# 1-Schematic_EMWAVER_DIY_V2.net
KiCad netlist of a schematic drawn in EasyEDA
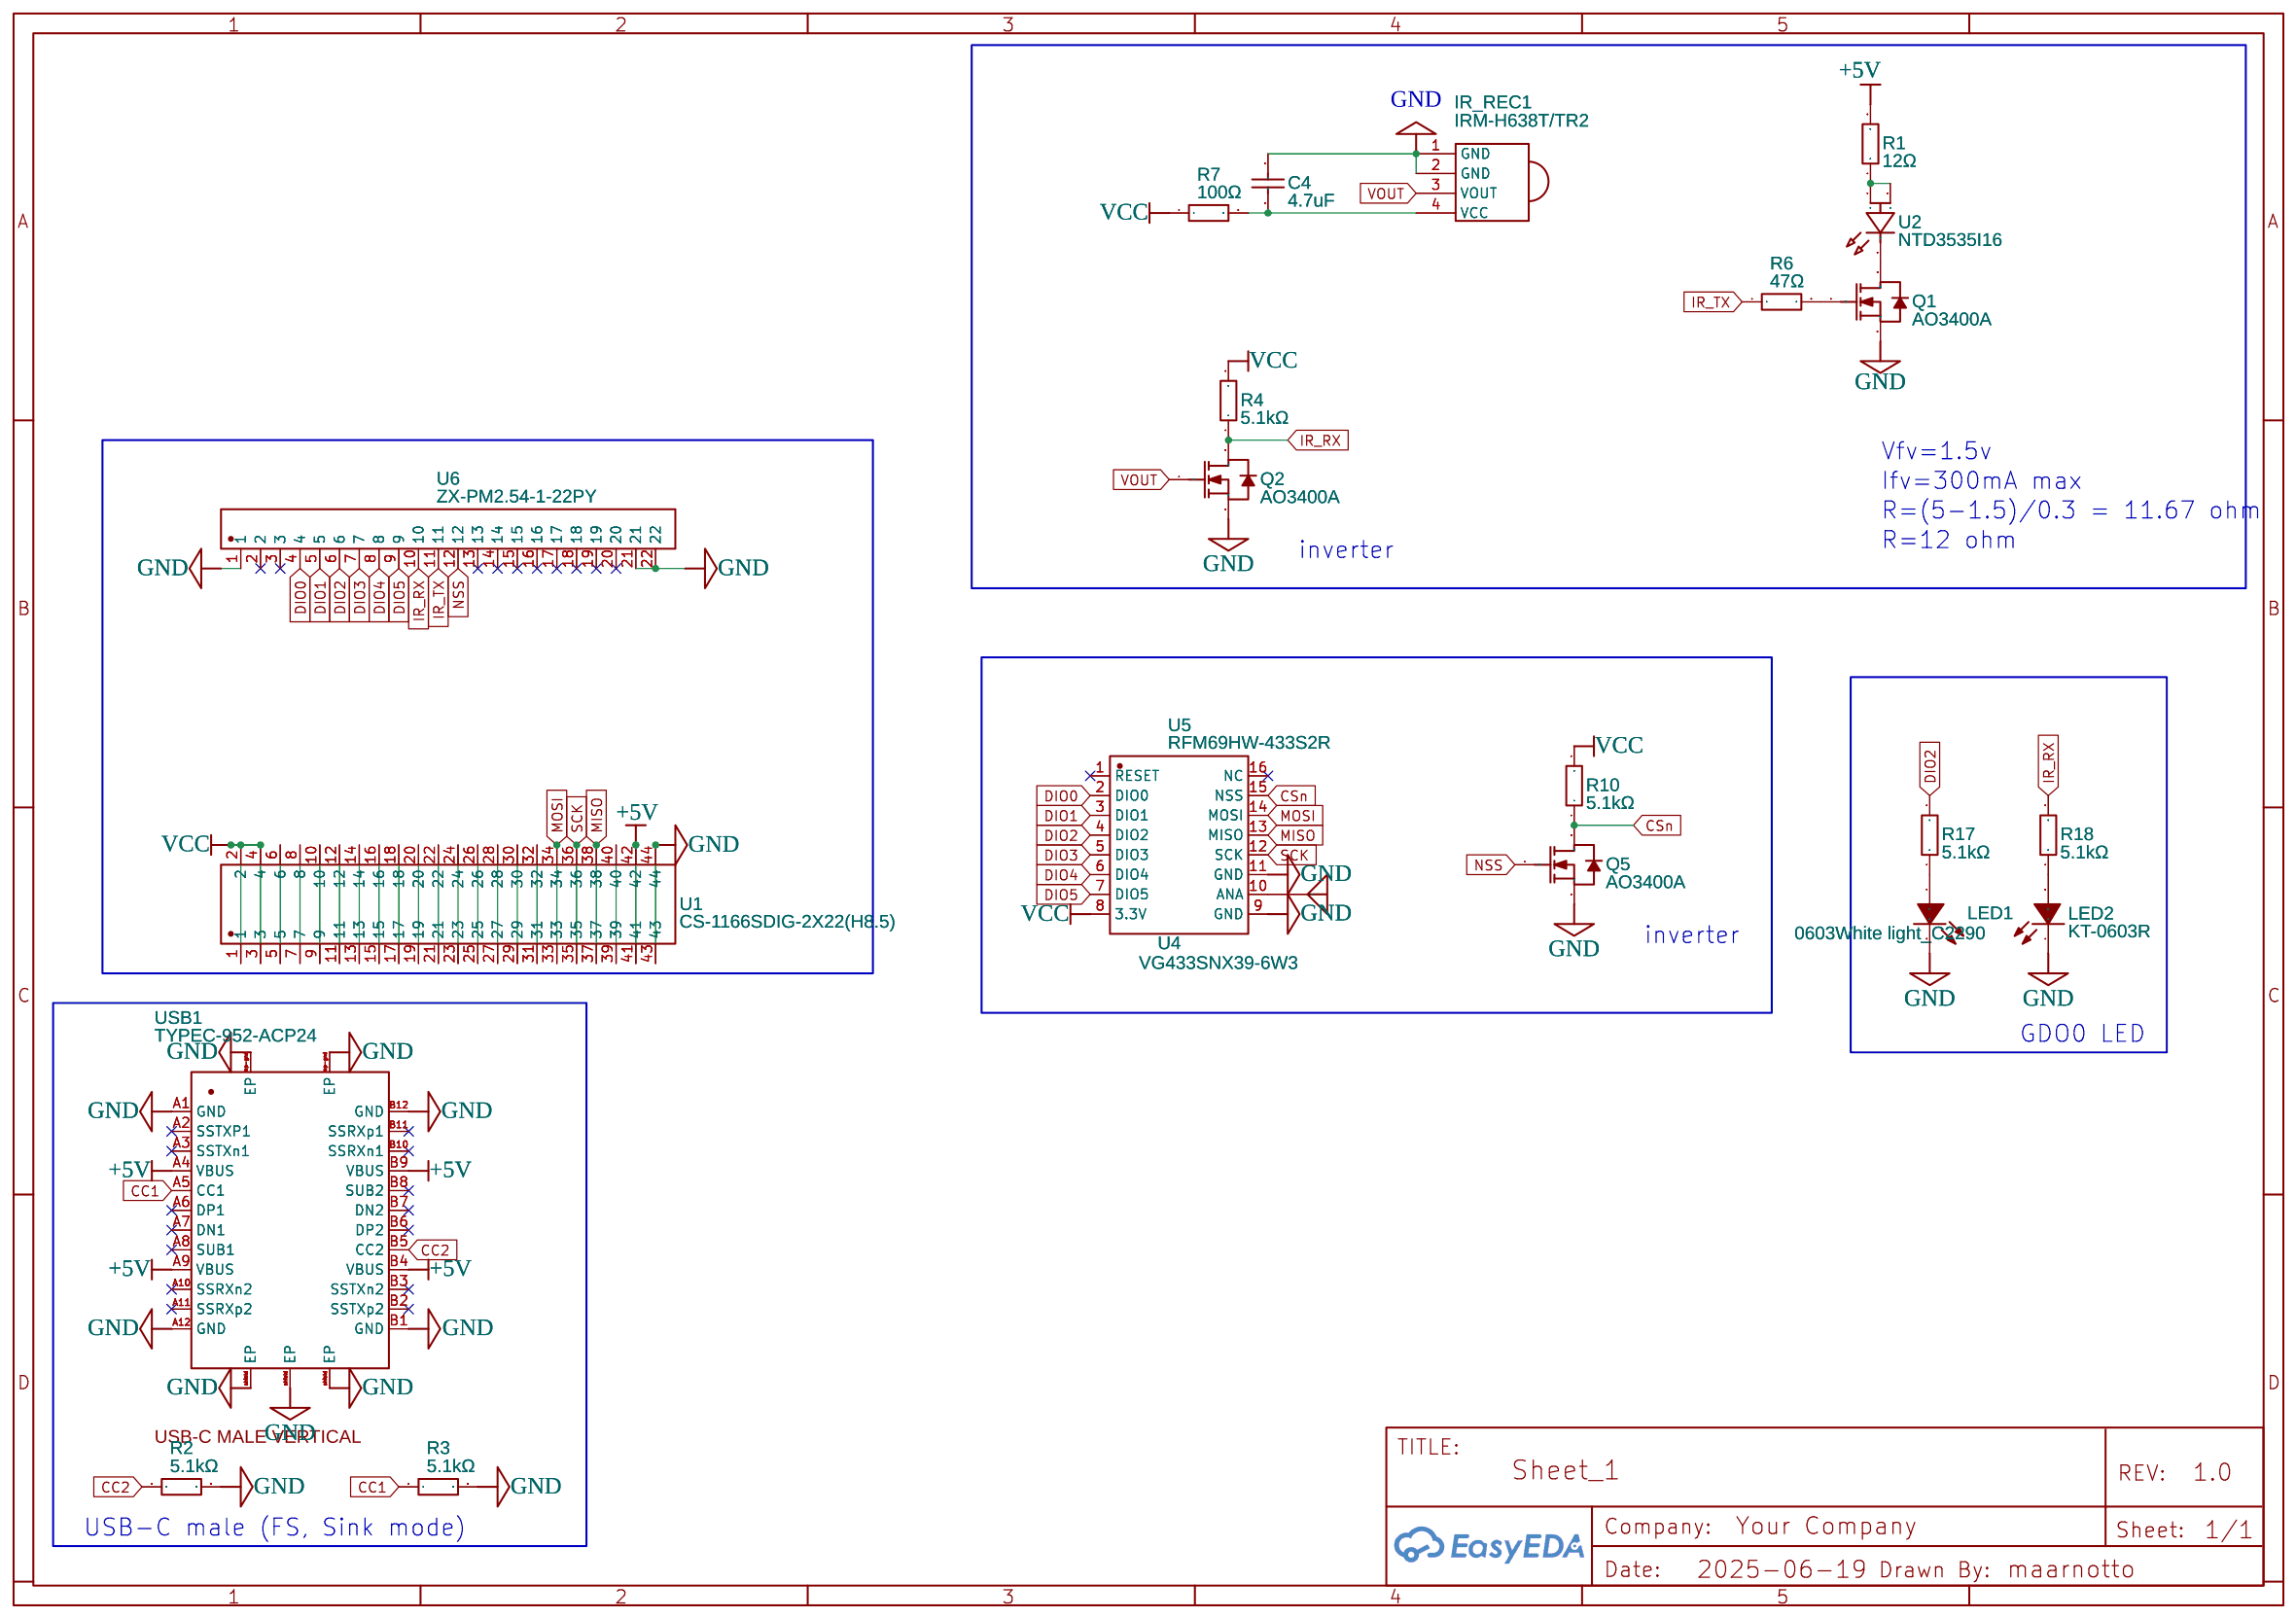
[diagram p0: schematic sheet]

(export (version "E")
  (design (tool "Eeschema 10.0.6"))
  (components
    (comp (ref "C4")
      (value "4.7uF")
      (fields
        (field (name "Manufacturer Part") "CL10A475KO8NNNC")
        (field (name "Manufacturer") "SAMSUNG(三星)")
      )
      (libsource (lib "") (part "CL10A475KO8NNNC"))
    )
    (comp (ref "IR_REC1")
      (value "IRM-H638T/TR2")
      (fields (field (name "Manufacturer") "EVERLIGHT(亿光)"))
      (libsource (lib "") (part "IRM-H638T/TR2"))
    )
    (comp (ref "LED1")
      (value "0603White light_C2290")
      (fields (field (name "Manufacturer Part") "KT-0603W") (field (name "Manufacturer") "KENTO"))
      (libsource (lib "") (part "0603White light_C2290"))
    )
    (comp (ref "LED2")
      (value "KT-0603R")
      (fields (field (name "Manufacturer") "KENTO"))
      (libsource (lib "") (part "KT-0603R"))
    )
    (comp (ref "Q1")
      (value "AO3400A")
      (fields (field (name "Manufacturer") "AOS"))
      (libsource (lib "") (part "AO3400A"))
    )
    (comp (ref "Q2")
      (value "AO3400A")
      (fields (field (name "Manufacturer") "AOS"))
      (libsource (lib "") (part "AO3400A"))
    )
    (comp (ref "Q5")
      (value "AO3400A")
      (fields (field (name "Manufacturer") "AOS"))
      (libsource (lib "") (part "AO3400A"))
    )
    (comp (ref "R1")
      (value "12Ω")
      (fields
        (field (name "Manufacturer Part") "25121WJ0120T4E")
        (field (name "Manufacturer") "UNI-ROYAL(厚声)")
      )
      (libsource (lib "") (part "25121WJ0120T4E"))
    )
    (comp (ref "R2")
      (value "5.1kΩ")
      (fields
        (field (name "Manufacturer Part") "0603WAF5101T5E")
        (field (name "Manufacturer") "UNI-ROYAL(厚声)")
      )
      (libsource (lib "") (part "0603WAF5101T5E_1"))
    )
    (comp (ref "R3")
      (value "5.1kΩ")
      (fields
        (field (name "Manufacturer Part") "0603WAF5101T5E")
        (field (name "Manufacturer") "UNI-ROYAL(厚声)")
      )
      (libsource (lib "") (part "0603WAF5101T5E_1"))
    )
    (comp (ref "R4")
      (value "5.1kΩ")
      (fields
        (field (name "Manufacturer Part") "0603WAF5101T5E")
        (field (name "Manufacturer") "UNI-ROYAL(厚声)")
      )
      (libsource (lib "") (part "0603WAF5101T5E"))
    )
    (comp (ref "R6")
      (value "47Ω")
      (fields
        (field (name "Manufacturer Part") "0805W8F470JT5E")
        (field (name "Manufacturer") "UNI-ROYAL(厚声)")
      )
      (libsource (lib "") (part "0805W8F470JT5E"))
    )
    (comp (ref "R7")
      (value "100Ω")
      (fields
        (field (name "Manufacturer Part") "0805W8F1000T5E")
        (field (name "Manufacturer") "UNI-ROYAL(厚声)")
      )
      (libsource (lib "") (part "0805W8F1000T5E"))
    )
    (comp (ref "R10")
      (value "5.1kΩ")
      (fields
        (field (name "Manufacturer Part") "0603WAF5101T5E")
        (field (name "Manufacturer") "UNI-ROYAL(厚声)")
      )
      (libsource (lib "") (part "0603WAF5101T5E"))
    )
    (comp (ref "R17")
      (value "5.1kΩ")
      (fields
        (field (name "Manufacturer Part") "0603WAF5101T5E")
        (field (name "Manufacturer") "UNI-ROYAL(厚声)")
      )
      (libsource (lib "") (part "0603WAF5101T5E"))
    )
    (comp (ref "R18")
      (value "5.1kΩ")
      (fields
        (field (name "Manufacturer Part") "0603WAF5101T5E")
        (field (name "Manufacturer") "UNI-ROYAL(厚声)")
      )
      (libsource (lib "") (part "0603WAF5101T5E"))
    )
    (comp (ref "U1")
      (value "CS-1166SDIG-2X22(H8.5)")
      (fields (field (name "Manufacturer") "CST(永丰盈)"))
      (libsource (lib "") (part "CS-1166SDIG-2X22(H8.5)"))
    )
    (comp (ref "U2")
      (value "NTD3535I16")
      (fields (field (name "Manufacturer") "国星光电"))
      (libsource (lib "") (part "NTD3535I16"))
    )
    (comp (ref "U4")
      (value "VG433SNX39-6W3")
      (fields (field (name "Manufacturer") "Vollgo(沃进)"))
      (libsource (lib "") (part "VG433SNX39-6W3"))
    )
    (comp (ref "U5") (value "RFM69HW-433S2R") (libsource (lib "") (part "RFM69HW-433S2R")))
    (comp (ref "U6")
      (value "ZX-PM2.54-1-22PY")
      (fields (field (name "Manufacturer") "Megastar(兆星)"))
      (libsource (lib "") (part "ZX-PM2.54-1-22PY"))
    )
    (comp (ref "USB1")
      (value "TYPEC-952-ACP24")
      (fields (field (name "Manufacturer") "XUNPU(讯普)"))
      (libsource (lib "") (part "TYPEC-952-ACP24"))
    )
  )
  (nets
    (net (code "1") (name "+5V") (class "Default")
      (node (ref "R1") (pin "2") (pinfunction "2_2") (pintype "input"))
      (node (ref "U1") (pin "41") (pinfunction "41_41") (pintype "unspecified"))
      (node (ref "U1") (pin "42") (pinfunction "42_42") (pintype "unspecified"))
      (node (ref "USB1") (pin "A4") (pinfunction "VBUS_A4") (pintype "unspecified"))
      (node (ref "USB1") (pin "A9") (pinfunction "VBUS_A9") (pintype "unspecified"))
      (node (ref "USB1") (pin "B4") (pinfunction "VBUS_B4") (pintype "unspecified"))
      (node (ref "USB1") (pin "B9") (pinfunction "VBUS_B9") (pintype "unspecified"))
    )
    (net (code "2") (name "CC1") (class "Default")
      (node (ref "R3") (pin "1") (pinfunction "1_1") (pintype "input"))
      (node (ref "USB1") (pin "A5") (pinfunction "CC1_A5") (pintype "unspecified"))
    )
    (net (code "3") (name "CC2") (class "Default")
      (node (ref "R2") (pin "1") (pinfunction "1_1") (pintype "input"))
      (node (ref "USB1") (pin "B5") (pinfunction "CC2_B5") (pintype "unspecified"))
    )
    (net (code "4") (name "CSn") (class "Default")
      (node (ref "Q5") (pin "3") (pinfunction "D_3") (pintype "unspecified"))
      (node (ref "R10") (pin "1") (pinfunction "1_1") (pintype "input"))
      (node (ref "U5") (pin "15") (pinfunction "NSS_15") (pintype "unspecified"))
    )
    (net (code "5") (name "DIO0") (class "Default")
      (node (ref "U5") (pin "2") (pinfunction "DIO0_2") (pintype "unspecified"))
      (node (ref "U6") (pin "4") (pinfunction "4_4") (pintype "unspecified"))
    )
    (net (code "6") (name "DIO1") (class "Default")
      (node (ref "U5") (pin "3") (pinfunction "DIO1_3") (pintype "unspecified"))
      (node (ref "U6") (pin "5") (pinfunction "5_5") (pintype "unspecified"))
    )
    (net (code "7") (name "DIO2") (class "Default")
      (node (ref "R17") (pin "2") (pinfunction "2_2") (pintype "input"))
      (node (ref "U5") (pin "4") (pinfunction "DIO2_4") (pintype "unspecified"))
      (node (ref "U6") (pin "6") (pinfunction "6_6") (pintype "unspecified"))
    )
    (net (code "8") (name "DIO3") (class "Default")
      (node (ref "U5") (pin "5") (pinfunction "DIO3_5") (pintype "unspecified"))
      (node (ref "U6") (pin "7") (pinfunction "7_7") (pintype "unspecified"))
    )
    (net (code "9") (name "DIO4") (class "Default")
      (node (ref "U5") (pin "6") (pinfunction "DIO4_6") (pintype "unspecified"))
      (node (ref "U6") (pin "8") (pinfunction "8_8") (pintype "unspecified"))
    )
    (net (code "10") (name "DIO5") (class "Default")
      (node (ref "U5") (pin "7") (pinfunction "DIO5_7") (pintype "unspecified"))
      (node (ref "U6") (pin "9") (pinfunction "9_9") (pintype "unspecified"))
    )
    (net (code "11") (name "GND") (class "Default")
      (node (ref "C4") (pin "2") (pinfunction "2_2") (pintype "input"))
      (node (ref "IR_REC1") (pin "1") (pinfunction "GND_1") (pintype "input"))
      (node (ref "IR_REC1") (pin "2") (pinfunction "GND_2") (pintype "input"))
      (node (ref "LED1") (pin "2") (pinfunction "K_2") (pintype "unspecified"))
      (node (ref "LED2") (pin "1") (pinfunction "K_1") (pintype "unspecified"))
      (node (ref "Q1") (pin "2") (pinfunction "S_2") (pintype "unspecified"))
      (node (ref "Q2") (pin "2") (pinfunction "S_2") (pintype "unspecified"))
      (node (ref "Q5") (pin "2") (pinfunction "S_2") (pintype "unspecified"))
      (node (ref "R2") (pin "2") (pinfunction "2_2") (pintype "input"))
      (node (ref "R3") (pin "2") (pinfunction "2_2") (pintype "input"))
      (node (ref "U1") (pin "43") (pinfunction "43_43") (pintype "unspecified"))
      (node (ref "U1") (pin "44") (pinfunction "44_44") (pintype "unspecified"))
      (node (ref "U5") (pin "11") (pinfunction "GND_11") (pintype "unspecified"))
      (node (ref "U5") (pin "9") (pinfunction "GND_9") (pintype "unspecified"))
      (node (ref "U6") (pin "1") (pinfunction "1_1") (pintype "unspecified"))
      (node (ref "U6") (pin "21") (pinfunction "21_21") (pintype "unspecified"))
      (node (ref "U6") (pin "22") (pinfunction "22_22") (pintype "unspecified"))
      (node (ref "USB1") (pin "A1") (pinfunction "GND_A1") (pintype "unspecified"))
      (node (ref "USB1") (pin "A12") (pinfunction "GND_A12") (pintype "unspecified"))
      (node (ref "USB1") (pin "B1") (pinfunction "GND_B1") (pintype "unspecified"))
      (node (ref "USB1") (pin "B12") (pinfunction "GND_B12") (pintype "unspecified"))
      (node (ref "USB1") (pin "mp-gnd") (pinfunction "EP_mp-gnd") (pintype "unspecified"))
      (node (ref "USB1") (pin "shield") (pinfunction "EP_shield") (pintype "unspecified"))
    )
    (net (code "12") (name "IR_RX") (class "Default")
      (node (ref "Q2") (pin "3") (pinfunction "D_3") (pintype "unspecified"))
      (node (ref "R18") (pin "2") (pinfunction "2_2") (pintype "input"))
      (node (ref "R4") (pin "1") (pinfunction "1_1") (pintype "input"))
      (node (ref "U6") (pin "10") (pinfunction "10_10") (pintype "unspecified"))
    )
    (net (code "13") (name "IR_TX") (class "Default")
      (node (ref "R6") (pin "1") (pinfunction "1_1") (pintype "input"))
      (node (ref "U6") (pin "11") (pinfunction "11_11") (pintype "unspecified"))
    )
    (net (code "14") (name "MISO") (class "Default")
      (node (ref "U1") (pin "37") (pinfunction "37_37") (pintype "unspecified"))
      (node (ref "U1") (pin "38") (pinfunction "38_38") (pintype "unspecified"))
      (node (ref "U5") (pin "13") (pinfunction "MISO_13") (pintype "unspecified"))
    )
    (net (code "15") (name "MOSI") (class "Default")
      (node (ref "U1") (pin "33") (pinfunction "33_33") (pintype "unspecified"))
      (node (ref "U1") (pin "34") (pinfunction "34_34") (pintype "unspecified"))
      (node (ref "U5") (pin "14") (pinfunction "MOSI_14") (pintype "unspecified"))
    )
    (net (code "16") (name "NSS") (class "Default")
      (node (ref "Q5") (pin "1") (pinfunction "G_1") (pintype "unspecified"))
      (node (ref "U6") (pin "12") (pinfunction "12_12") (pintype "unspecified"))
    )
    (net (code "17") (name "Net-(IR_REC1-VCC)") (class "Default")
      (node (ref "C4") (pin "1") (pinfunction "1_1") (pintype "input"))
      (node (ref "IR_REC1") (pin "4") (pinfunction "VCC_4") (pintype "input"))
      (node (ref "R7") (pin "2") (pinfunction "2_2") (pintype "input"))
    )
    (net (code "18") (name "Net-(LED1-A)") (class "Default")
      (node (ref "LED1") (pin "1") (pinfunction "A_1") (pintype "unspecified"))
      (node (ref "R17") (pin "1") (pinfunction "1_1") (pintype "input"))
    )
    (net (code "19") (name "Net-(LED2-A)") (class "Default")
      (node (ref "LED2") (pin "2") (pinfunction "A_2") (pintype "unspecified"))
      (node (ref "R18") (pin "1") (pinfunction "1_1") (pintype "input"))
    )
    (net (code "20") (name "Net-(Q1-D)") (class "Default")
      (node (ref "Q1") (pin "3") (pinfunction "D_3") (pintype "unspecified"))
      (node (ref "U2") (pin "3") (pinfunction "K_3") (pintype "unspecified"))
    )
    (net (code "21") (name "Net-(Q1-G)") (class "Default")
      (node (ref "Q1") (pin "1") (pinfunction "G_1") (pintype "unspecified"))
      (node (ref "R6") (pin "2") (pinfunction "2_2") (pintype "input"))
    )
    (net (code "22") (name "Net-(U1-Pad5)") (class "Default")
      (node (ref "U1") (pin "5") (pinfunction "5_5") (pintype "unspecified"))
      (node (ref "U1") (pin "6") (pinfunction "6_6") (pintype "unspecified"))
    )
    (net (code "23") (name "Net-(U1-Pad7)") (class "Default")
      (node (ref "U1") (pin "7") (pinfunction "7_7") (pintype "unspecified"))
      (node (ref "U1") (pin "8") (pinfunction "8_8") (pintype "unspecified"))
    )
    (net (code "24") (name "Net-(U1-Pad10)") (class "Default")
      (node (ref "U1") (pin "10") (pinfunction "10_10") (pintype "unspecified"))
      (node (ref "U1") (pin "9") (pinfunction "9_9") (pintype "unspecified"))
    )
    (net (code "25") (name "Net-(U1-Pad11)") (class "Default")
      (node (ref "U1") (pin "11") (pinfunction "11_11") (pintype "unspecified"))
      (node (ref "U1") (pin "12") (pinfunction "12_12") (pintype "unspecified"))
    )
    (net (code "26") (name "Net-(U1-Pad13)") (class "Default")
      (node (ref "U1") (pin "13") (pinfunction "13_13") (pintype "unspecified"))
      (node (ref "U1") (pin "14") (pinfunction "14_14") (pintype "unspecified"))
    )
    (net (code "27") (name "Net-(U1-Pad15)") (class "Default")
      (node (ref "U1") (pin "15") (pinfunction "15_15") (pintype "unspecified"))
      (node (ref "U1") (pin "16") (pinfunction "16_16") (pintype "unspecified"))
    )
    (net (code "28") (name "Net-(U1-Pad17)") (class "Default")
      (node (ref "U1") (pin "17") (pinfunction "17_17") (pintype "unspecified"))
      (node (ref "U1") (pin "18") (pinfunction "18_18") (pintype "unspecified"))
    )
    (net (code "29") (name "Net-(U1-Pad19)") (class "Default")
      (node (ref "U1") (pin "19") (pinfunction "19_19") (pintype "unspecified"))
      (node (ref "U1") (pin "20") (pinfunction "20_20") (pintype "unspecified"))
    )
    (net (code "30") (name "Net-(U1-Pad21)") (class "Default")
      (node (ref "U1") (pin "21") (pinfunction "21_21") (pintype "unspecified"))
      (node (ref "U1") (pin "22") (pinfunction "22_22") (pintype "unspecified"))
    )
    (net (code "31") (name "Net-(U1-Pad23)") (class "Default")
      (node (ref "U1") (pin "23") (pinfunction "23_23") (pintype "unspecified"))
      (node (ref "U1") (pin "24") (pinfunction "24_24") (pintype "unspecified"))
    )
    (net (code "32") (name "Net-(U1-Pad25)") (class "Default")
      (node (ref "U1") (pin "25") (pinfunction "25_25") (pintype "unspecified"))
      (node (ref "U1") (pin "26") (pinfunction "26_26") (pintype "unspecified"))
    )
    (net (code "33") (name "Net-(U1-Pad27)") (class "Default")
      (node (ref "U1") (pin "27") (pinfunction "27_27") (pintype "unspecified"))
      (node (ref "U1") (pin "28") (pinfunction "28_28") (pintype "unspecified"))
    )
    (net (code "34") (name "Net-(U1-Pad29)") (class "Default")
      (node (ref "U1") (pin "29") (pinfunction "29_29") (pintype "unspecified"))
      (node (ref "U1") (pin "30") (pinfunction "30_30") (pintype "unspecified"))
    )
    (net (code "35") (name "Net-(U1-Pad31)") (class "Default")
      (node (ref "U1") (pin "31") (pinfunction "31_31") (pintype "unspecified"))
      (node (ref "U1") (pin "32") (pinfunction "32_32") (pintype "unspecified"))
    )
    (net (code "36") (name "Net-(U1-Pad39)") (class "Default")
      (node (ref "U1") (pin "39") (pinfunction "39_39") (pintype "unspecified"))
      (node (ref "U1") (pin "40") (pinfunction "40_40") (pintype "unspecified"))
    )
    (net (code "37") (name "Net-(U2-A)") (class "Default")
      (node (ref "R1") (pin "1") (pinfunction "1_1") (pintype "input"))
      (node (ref "U2") (pin "1") (pinfunction "A_1") (pintype "unspecified"))
      (node (ref "U2") (pin "2") (pinfunction "2_2") (pintype "unspecified"))
    )
    (net (code "38") (name "Net-(U5-ANA)") (class "Default")
      (node (ref "U4") (pin "1") (pinfunction "1_1") (pintype "unspecified"))
      (node (ref "U5") (pin "10") (pinfunction "ANA_10") (pintype "unspecified"))
    )
    (net (code "39") (name "SCK") (class "Default")
      (node (ref "U1") (pin "35") (pinfunction "35_35") (pintype "unspecified"))
      (node (ref "U1") (pin "36") (pinfunction "36_36") (pintype "unspecified"))
      (node (ref "U5") (pin "12") (pinfunction "SCK_12") (pintype "unspecified"))
    )
    (net (code "40") (name "VCC") (class "Default")
      (node (ref "R10") (pin "2") (pinfunction "2_2") (pintype "input"))
      (node (ref "R4") (pin "2") (pinfunction "2_2") (pintype "input"))
      (node (ref "R7") (pin "1") (pinfunction "1_1") (pintype "input"))
      (node (ref "U1") (pin "1") (pinfunction "1_1") (pintype "unspecified"))
      (node (ref "U1") (pin "2") (pinfunction "2_2") (pintype "unspecified"))
      (node (ref "U1") (pin "3") (pinfunction "3_3") (pintype "unspecified"))
      (node (ref "U1") (pin "4") (pinfunction "4_4") (pintype "unspecified"))
      (node (ref "U5") (pin "8") (pinfunction "3.3V_8") (pintype "unspecified"))
    )
    (net (code "41") (name "VOUT") (class "Default")
      (node (ref "IR_REC1") (pin "3") (pinfunction "VOUT_3") (pintype "input"))
      (node (ref "Q2") (pin "1") (pinfunction "G_1") (pintype "unspecified"))
    )
    (net (code "42") (name "unconnected-(U5-NC-Pad16)") (class "Default")
      (node (ref "U5") (pin "16") (pinfunction "NC_16") (pintype "unspecified+no_connect"))
    )
    (net (code "43") (name "unconnected-(U5-RESET-Pad1)") (class "Default")
      (node (ref "U5") (pin "1") (pinfunction "RESET_1") (pintype "unspecified+no_connect"))
    )
    (net (code "44") (name "unconnected-(U6-Pad2)") (class "Default")
      (node (ref "U6") (pin "2") (pinfunction "2_2") (pintype "unspecified+no_connect"))
    )
    (net (code "45") (name "unconnected-(U6-Pad3)") (class "Default")
      (node (ref "U6") (pin "3") (pinfunction "3_3") (pintype "unspecified+no_connect"))
    )
    (net (code "46") (name "unconnected-(U6-Pad13)") (class "Default")
      (node (ref "U6") (pin "13") (pinfunction "13_13") (pintype "unspecified+no_connect"))
    )
    (net (code "47") (name "unconnected-(U6-Pad14)") (class "Default")
      (node (ref "U6") (pin "14") (pinfunction "14_14") (pintype "unspecified+no_connect"))
    )
    (net (code "48") (name "unconnected-(U6-Pad15)") (class "Default")
      (node (ref "U6") (pin "15") (pinfunction "15_15") (pintype "unspecified+no_connect"))
    )
    (net (code "49") (name "unconnected-(U6-Pad16)") (class "Default")
      (node (ref "U6") (pin "16") (pinfunction "16_16") (pintype "unspecified+no_connect"))
    )
    (net (code "50") (name "unconnected-(U6-Pad17)") (class "Default")
      (node (ref "U6") (pin "17") (pinfunction "17_17") (pintype "unspecified+no_connect"))
    )
    (net (code "51") (name "unconnected-(U6-Pad18)") (class "Default")
      (node (ref "U6") (pin "18") (pinfunction "18_18") (pintype "unspecified+no_connect"))
    )
    (net (code "52") (name "unconnected-(U6-Pad19)") (class "Default")
      (node (ref "U6") (pin "19") (pinfunction "19_19") (pintype "unspecified+no_connect"))
    )
    (net (code "53") (name "unconnected-(U6-Pad20)") (class "Default")
      (node (ref "U6") (pin "20") (pinfunction "20_20") (pintype "unspecified+no_connect"))
    )
    (net (code "54") (name "unconnected-(USB1-DN1-PadA7)") (class "Default")
      (node (ref "USB1") (pin "A7") (pinfunction "DN1_A7") (pintype "unspecified+no_connect"))
    )
    (net (code "55") (name "unconnected-(USB1-DN2-PadB7)") (class "Default")
      (node (ref "USB1") (pin "B7") (pinfunction "DN2_B7") (pintype "unspecified+no_connect"))
    )
    (net (code "56") (name "unconnected-(USB1-DP1-PadA6)") (class "Default")
      (node (ref "USB1") (pin "A6") (pinfunction "DP1_A6") (pintype "unspecified+no_connect"))
    )
    (net (code "57") (name "unconnected-(USB1-DP2-PadB6)") (class "Default")
      (node (ref "USB1") (pin "B6") (pinfunction "DP2_B6") (pintype "unspecified+no_connect"))
    )
    (net (code "58") (name "unconnected-(USB1-SSRXn1-PadB10)") (class "Default")
      (node (ref "USB1") (pin "B10") (pinfunction "SSRXn1_B10") (pintype "unspecified+no_connect"))
    )
    (net (code "59") (name "unconnected-(USB1-SSRXn2-PadA10)") (class "Default")
      (node (ref "USB1") (pin "A10") (pinfunction "SSRXn2_A10") (pintype "unspecified+no_connect"))
    )
    (net (code "60") (name "unconnected-(USB1-SSRXp1-PadB11)") (class "Default")
      (node (ref "USB1") (pin "B11") (pinfunction "SSRXp1_B11") (pintype "unspecified+no_connect"))
    )
    (net (code "61") (name "unconnected-(USB1-SSRXp2-PadA11)") (class "Default")
      (node (ref "USB1") (pin "A11") (pinfunction "SSRXp2_A11") (pintype "unspecified+no_connect"))
    )
    (net (code "62") (name "unconnected-(USB1-SSTXP1-PadA2)") (class "Default")
      (node (ref "USB1") (pin "A2") (pinfunction "SSTXP1_A2") (pintype "unspecified+no_connect"))
    )
    (net (code "63") (name "unconnected-(USB1-SSTXn1-PadA3)") (class "Default")
      (node (ref "USB1") (pin "A3") (pinfunction "SSTXn1_A3") (pintype "unspecified+no_connect"))
    )
    (net (code "64") (name "unconnected-(USB1-SSTXn2-PadB3)") (class "Default")
      (node (ref "USB1") (pin "B3") (pinfunction "SSTXn2_B3") (pintype "unspecified+no_connect"))
    )
    (net (code "65") (name "unconnected-(USB1-SSTXp2-PadB2)") (class "Default")
      (node (ref "USB1") (pin "B2") (pinfunction "SSTXp2_B2") (pintype "unspecified+no_connect"))
    )
    (net (code "66") (name "unconnected-(USB1-SUB1-PadA8)") (class "Default")
      (node (ref "USB1") (pin "A8") (pinfunction "SUB1_A8") (pintype "unspecified+no_connect"))
    )
    (net (code "67") (name "unconnected-(USB1-SUB2-PadB8)") (class "Default")
      (node (ref "USB1") (pin "B8") (pinfunction "SUB2_B8") (pintype "unspecified+no_connect"))
    )
  )
)
